# potinho.net
KiCad netlist of a schematic drawn in EAGLE
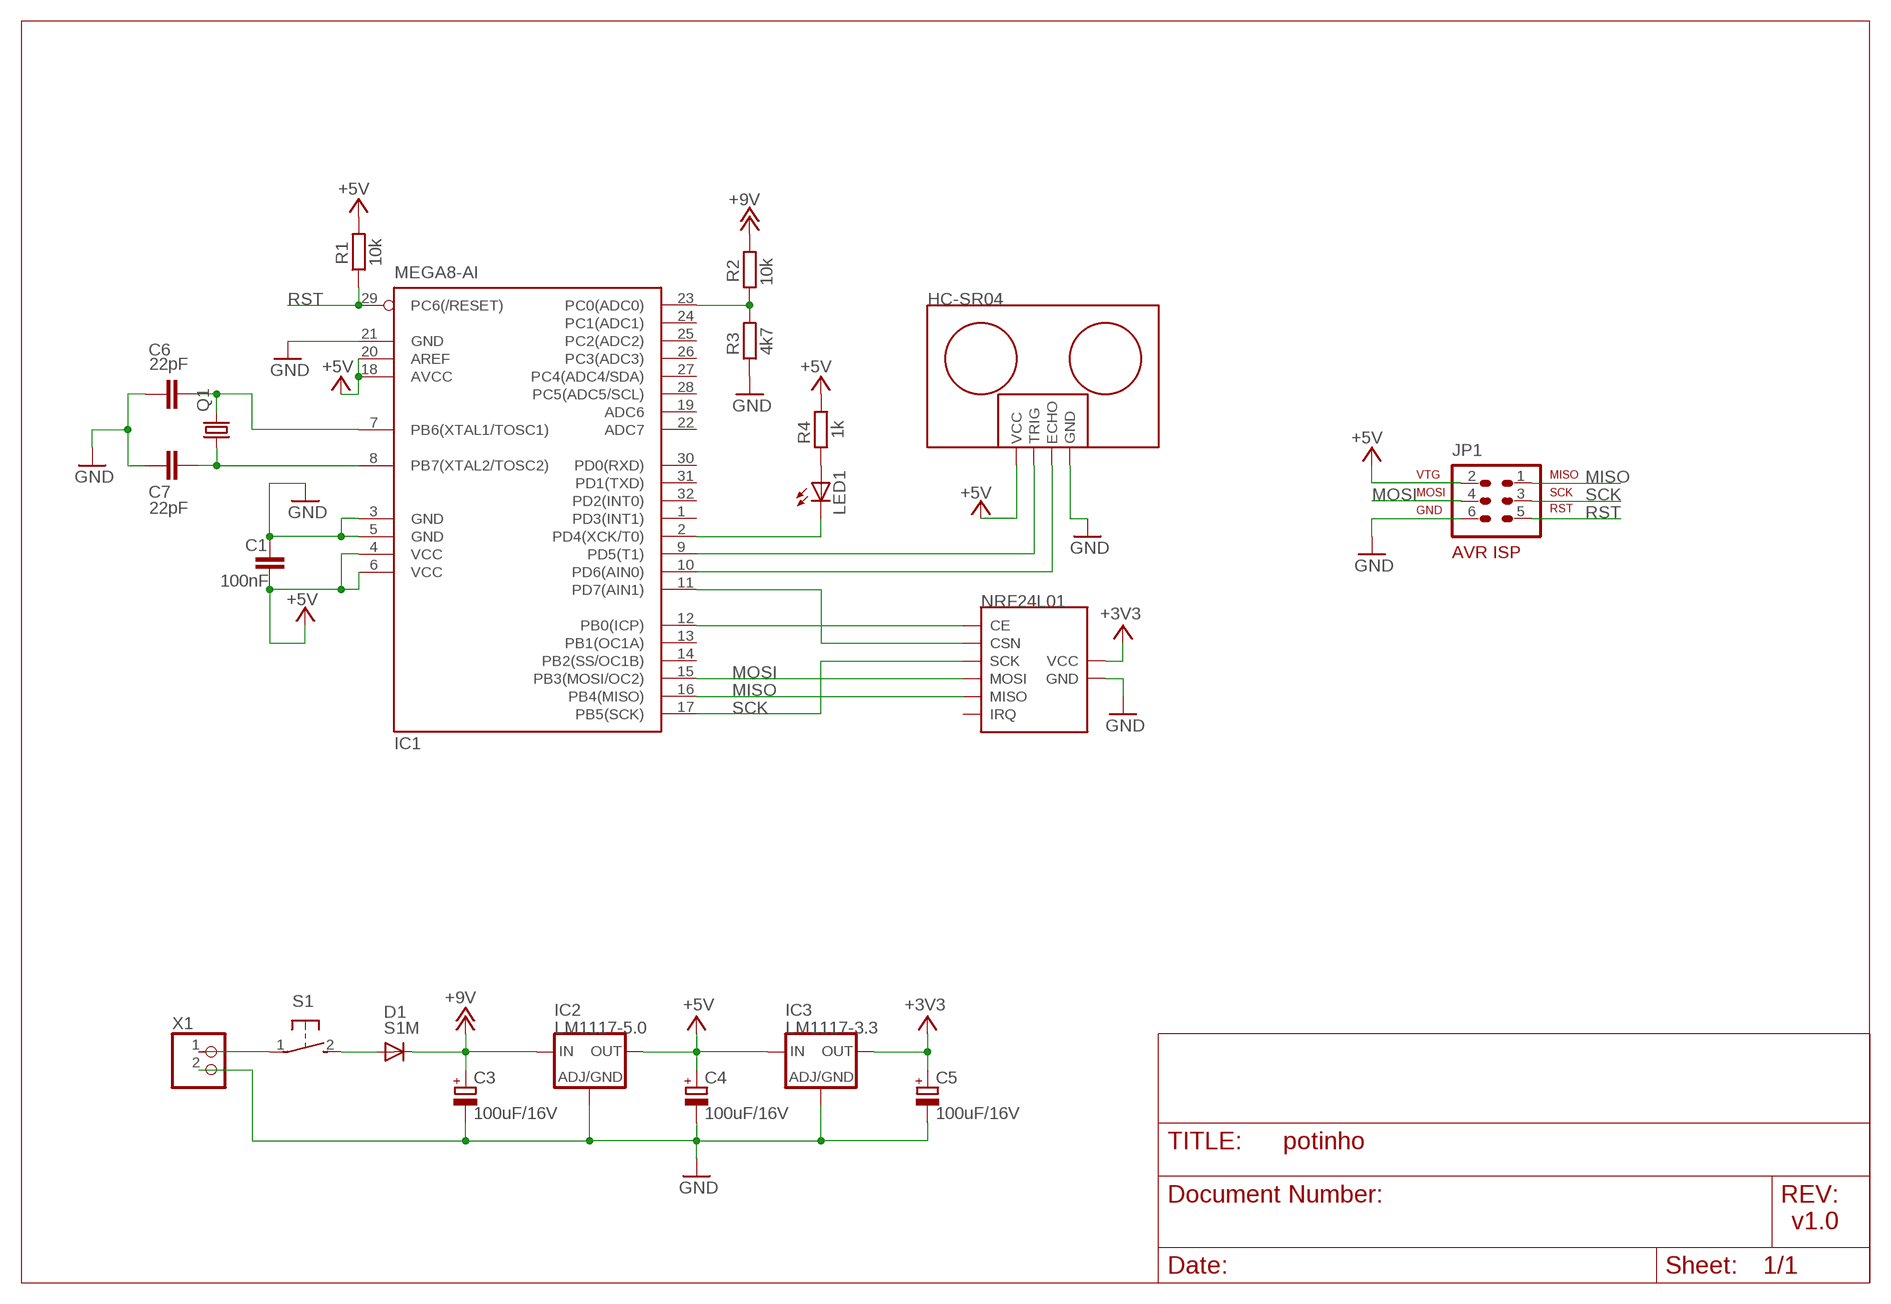
[diagram p0: schematic, sheet 1]

(export (version "E")
  (design (tool "Eeschema 10.0.6"))
  (components
    (comp (ref "C1")
      (value "100nF")
      (footprint "eagle-import:C0805K")
      (libsource (lib "eagle-import") (part "C-EUC0805K"))
    )
    (comp (ref "C3")
      (value "100uF/16V")
      (footprint "eagle-import:PANASONIC_D")
      (libsource (lib "eagle-import") (part "CPOL-EUPD"))
    )
    (comp (ref "C4")
      (value "100uF/16V")
      (footprint "eagle-import:PANASONIC_D")
      (libsource (lib "eagle-import") (part "CPOL-EUPD"))
    )
    (comp (ref "C5")
      (value "100uF/16V")
      (footprint "eagle-import:PANASONIC_D")
      (libsource (lib "eagle-import") (part "CPOL-EUPD"))
    )
    (comp (ref "C6")
      (value "22pF")
      (footprint "eagle-import:C0805K")
      (libsource (lib "eagle-import") (part "C-EUC0805K"))
    )
    (comp (ref "C7")
      (value "22pF")
      (footprint "eagle-import:C0805K")
      (libsource (lib "eagle-import") (part "C-EUC0805K"))
    )
    (comp (ref "D1")
      (value "S1M")
      (footprint "eagle-import:DO-214AC")
      (libsource (lib "eagle-import") (part "S1M"))
    )
    (comp (ref "IC1")
      (value "MEGA8-AI")
      (footprint "eagle-import:TQFP32-08")
      (fields (field (name "MPN") "ATMEGA8-16AU"))
      (libsource (lib "eagle-import") (part "MEGA8-AI"))
    )
    (comp (ref "IC2")
      (value "LM1117-5.0")
      (footprint "eagle-import:SOT223")
      (libsource (lib "eagle-import") (part "LM1117S"))
    )
    (comp (ref "IC3")
      (value "LM1117-3.3")
      (footprint "eagle-import:SOT223")
      (libsource (lib "eagle-import") (part "LM1117S"))
    )
    (comp (ref "IC4")
      (value "NRF24L01")
      (footprint "eagle-import:NRF24L01-MODULE")
      (libsource (lib "eagle-import") (part "NRF24L01-MODULE"))
    )
    (comp (ref "IC31")
      (value "HC-SR04")
      (footprint "eagle-import:1X04")
      (libsource (lib "eagle-import") (part "HC-SR04"))
    )
    (comp (ref "JP1")
      (value "AVR-ISP-6")
      (footprint "eagle-import:AVR-ISP-6")
      (libsource (lib "eagle-import") (part "AVR-ISP-6"))
    )
    (comp (ref "LED1")
      (value "LED3MM")
      (footprint "eagle-import:LED3MM")
      (libsource (lib "eagle-import") (part "LED3MM"))
    )
    (comp (ref "Q1")
      (value "CRYSTALHC49UP")
      (footprint "eagle-import:HC49UP")
      (libsource (lib "eagle-import") (part "CRYSTALHC49UP"))
    )
    (comp (ref "R1")
      (value "10k")
      (footprint "eagle-import:R0805")
      (libsource (lib "eagle-import") (part "R-EU_R0805"))
    )
    (comp (ref "R2")
      (value "10k")
      (footprint "eagle-import:0207_7")
      (libsource (lib "eagle-import") (part "R-EU_7"))
    )
    (comp (ref "R3")
      (value "4k7")
      (footprint "eagle-import:0207_7")
      (libsource (lib "eagle-import") (part "R-EU_7"))
    )
    (comp (ref "R4")
      (value "1k")
      (footprint "eagle-import:0207_7")
      (libsource (lib "eagle-import") (part "R-EU_7"))
    )
    (comp (ref "S1")
      (value "31-XX")
      (footprint "eagle-import:B3F-31XX")
      (fields (field (name "MPN") "B3F-3100"))
      (libsource (lib "eagle-import") (part "31-XX"))
    )
    (comp (ref "X1")
      (value "W237-102")
      (footprint "eagle-import:W237-102")
      (libsource (lib "eagle-import") (part "W237-102"))
    )
  )
  (nets
    (net (code "1") (name "+3V3") (class "Default")
      (node (ref "C5") (pin "+") (pinfunction "+_+") (pintype "passive"))
      (node (ref "IC3") (pin "2") (pinfunction "OUT_2") (pintype "passive"))
      (node (ref "IC3") (pin "4") (pinfunction "OUT_4") (pintype "passive"))
      (node (ref "IC4") (pin "2") (pinfunction "VCC_2") (pintype "power_in"))
    )
    (net (code "2") (name "+5V") (class "Default")
      (node (ref "C1") (pin "2") (pinfunction "2_2") (pintype "passive"))
      (node (ref "C4") (pin "+") (pinfunction "+_+") (pintype "passive"))
      (node (ref "IC1") (pin "18") (pinfunction "AVCC_18") (pintype "power_in"))
      (node (ref "IC1") (pin "20") (pinfunction "AREF_20") (pintype "passive"))
      (node (ref "IC1") (pin "4") (pinfunction "VCC_4") (pintype "power_in"))
      (node (ref "IC1") (pin "6") (pinfunction "VCC_6") (pintype "power_in"))
      (node (ref "IC2") (pin "2") (pinfunction "OUT_2") (pintype "passive"))
      (node (ref "IC2") (pin "4") (pinfunction "OUT_4") (pintype "passive"))
      (node (ref "IC3") (pin "3") (pinfunction "IN_3") (pintype "input"))
      (node (ref "IC31") (pin "1") (pinfunction "VCC_1") (pintype "power_in"))
      (node (ref "JP1") (pin "2") (pinfunction "VTG_2") (pintype "passive"))
      (node (ref "R1") (pin "2") (pinfunction "2_2") (pintype "passive"))
      (node (ref "R4") (pin "2") (pinfunction "2_2") (pintype "passive"))
    )
    (net (code "3") (name "+9V") (class "Default")
      (node (ref "C3") (pin "+") (pinfunction "+_+") (pintype "passive"))
      (node (ref "D1") (pin "C") (pinfunction "C_C") (pintype "passive"))
      (node (ref "IC2") (pin "3") (pinfunction "IN_3") (pintype "input"))
      (node (ref "R2") (pin "2") (pinfunction "2_2") (pintype "passive"))
    )
    (net (code "4") (name "/MISO") (class "Default")
      (node (ref "IC1") (pin "16") (pinfunction "PB4(MISO)_16") (pintype "bidirectional"))
      (node (ref "IC4") (pin "7") (pinfunction "MISO_7") (pintype "bidirectional"))
      (node (ref "JP1") (pin "1") (pinfunction "MISO_1") (pintype "passive"))
    )
    (net (code "5") (name "/MOSI") (class "Default")
      (node (ref "IC1") (pin "15") (pinfunction "PB3(MOSI/OC2)_15") (pintype "bidirectional"))
      (node (ref "IC4") (pin "6") (pinfunction "MOSI_6") (pintype "bidirectional"))
      (node (ref "JP1") (pin "4") (pinfunction "MOSI_4") (pintype "passive"))
    )
    (net (code "6") (name "/RST") (class "Default")
      (node (ref "IC1") (pin "29") (pinfunction "PC6(/RESET)_29") (pintype "bidirectional"))
      (node (ref "JP1") (pin "5") (pinfunction "RST_5") (pintype "passive"))
      (node (ref "R1") (pin "1") (pinfunction "1_1") (pintype "passive"))
    )
    (net (code "7") (name "/SCK") (class "Default")
      (node (ref "IC1") (pin "17") (pinfunction "PB5(SCK)_17") (pintype "bidirectional"))
      (node (ref "IC4") (pin "5") (pinfunction "SCK_5") (pintype "bidirectional"))
      (node (ref "JP1") (pin "3") (pinfunction "SCK_3") (pintype "passive"))
    )
    (net (code "8") (name "GND") (class "Default")
      (node (ref "C1") (pin "1") (pinfunction "1_1") (pintype "passive"))
      (node (ref "C3") (pin "-") (pinfunction "-_-") (pintype "passive"))
      (node (ref "C4") (pin "-") (pinfunction "-_-") (pintype "passive"))
      (node (ref "C5") (pin "-") (pinfunction "-_-") (pintype "passive"))
      (node (ref "C6") (pin "1") (pinfunction "1_1") (pintype "passive"))
      (node (ref "C7") (pin "1") (pinfunction "1_1") (pintype "passive"))
      (node (ref "IC1") (pin "21") (pinfunction "GND_21") (pintype "power_in"))
      (node (ref "IC1") (pin "3") (pinfunction "GND_3") (pintype "power_in"))
      (node (ref "IC1") (pin "5") (pinfunction "GND_5") (pintype "power_in"))
      (node (ref "IC2") (pin "1") (pinfunction "ADJ_1") (pintype "input"))
      (node (ref "IC3") (pin "1") (pinfunction "ADJ_1") (pintype "input"))
      (node (ref "IC31") (pin "4") (pinfunction "GND_4") (pintype "power_in"))
      (node (ref "IC4") (pin "1") (pinfunction "GND_1") (pintype "power_in"))
      (node (ref "JP1") (pin "6") (pinfunction "GND_6") (pintype "passive"))
      (node (ref "R3") (pin "1") (pinfunction "1_1") (pintype "passive"))
      (node (ref "X1") (pin "2") (pinfunction "2_2") (pintype "passive"))
    )
    (net (code "9") (name "Net-(IC1-PB0(ICP))") (class "Default")
      (node (ref "IC1") (pin "12") (pinfunction "PB0(ICP)_12") (pintype "bidirectional"))
      (node (ref "IC4") (pin "3") (pinfunction "CE_3") (pintype "bidirectional"))
    )
    (net (code "10") (name "Net-(IC1-PB6(XTAL1{slash}TOSC1))") (class "Default")
      (node (ref "C6") (pin "2") (pinfunction "2_2") (pintype "passive"))
      (node (ref "IC1") (pin "7") (pinfunction "PB6(XTAL1/TOSC1)_7") (pintype "bidirectional"))
      (node (ref "Q1") (pin "2") (pinfunction "2_2") (pintype "passive"))
    )
    (net (code "11") (name "Net-(IC1-PB7(XTAL2{slash}TOSC2))") (class "Default")
      (node (ref "C7") (pin "2") (pinfunction "2_2") (pintype "passive"))
      (node (ref "IC1") (pin "8") (pinfunction "PB7(XTAL2/TOSC2)_8") (pintype "bidirectional"))
      (node (ref "Q1") (pin "1") (pinfunction "1_1") (pintype "passive"))
    )
    (net (code "12") (name "Net-(IC1-PC0(ADC0))") (class "Default")
      (node (ref "IC1") (pin "23") (pinfunction "PC0(ADC0)_23") (pintype "bidirectional"))
      (node (ref "R2") (pin "1") (pinfunction "1_1") (pintype "passive"))
      (node (ref "R3") (pin "2") (pinfunction "2_2") (pintype "passive"))
    )
    (net (code "13") (name "Net-(IC1-PD4(XCK{slash}T0))") (class "Default")
      (node (ref "IC1") (pin "2") (pinfunction "PD4(XCK/T0)_2") (pintype "bidirectional"))
      (node (ref "LED1") (pin "K") (pinfunction "C_K") (pintype "passive"))
    )
    (net (code "14") (name "Net-(IC1-PD5(T1))") (class "Default")
      (node (ref "IC1") (pin "9") (pinfunction "PD5(T1)_9") (pintype "bidirectional"))
      (node (ref "IC31") (pin "2") (pinfunction "TRIG_2") (pintype "bidirectional"))
    )
    (net (code "15") (name "Net-(IC1-PD6(AIN0))") (class "Default")
      (node (ref "IC1") (pin "10") (pinfunction "PD6(AIN0)_10") (pintype "bidirectional"))
      (node (ref "IC31") (pin "3") (pinfunction "ECHO_3") (pintype "bidirectional"))
    )
    (net (code "16") (name "Net-(IC1-PD7(AIN1))") (class "Default")
      (node (ref "IC1") (pin "11") (pinfunction "PD7(AIN1)_11") (pintype "bidirectional"))
      (node (ref "IC4") (pin "4") (pinfunction "CSN_4") (pintype "bidirectional"))
    )
    (net (code "17") (name "Net-(LED1-PadA)") (class "Default")
      (node (ref "LED1") (pin "A") (pinfunction "A_A") (pintype "passive"))
      (node (ref "R4") (pin "1") (pinfunction "1_1") (pintype "passive"))
    )
    (net (code "18") (name "Net-(S1-P)") (class "Default")
      (node (ref "S1") (pin "1") (pinfunction "P_1") (pintype "passive"))
      (node (ref "X1") (pin "1") (pinfunction "1_1") (pintype "passive"))
    )
    (net (code "19") (name "Net-(S1-S)") (class "Default")
      (node (ref "D1") (pin "A") (pinfunction "A_A") (pintype "passive"))
      (node (ref "S1") (pin "2") (pinfunction "S_2") (pintype "passive"))
    )
    (net (code "20") (name "unconnected-(IC1-ADC6-Pad19)") (class "Default")
      (node (ref "IC1") (pin "19") (pinfunction "ADC6_19") (pintype "bidirectional"))
    )
    (net (code "21") (name "unconnected-(IC1-ADC7-Pad22)") (class "Default")
      (node (ref "IC1") (pin "22") (pinfunction "ADC7_22") (pintype "bidirectional"))
    )
    (net (code "22") (name "unconnected-(IC1-PB1(OC1A)-Pad13)") (class "Default")
      (node (ref "IC1") (pin "13") (pinfunction "PB1(OC1A)_13") (pintype "bidirectional"))
    )
    (net (code "23") (name "unconnected-(IC1-PB2(SS{slash}OC1B)-Pad14)") (class "Default")
      (node (ref "IC1") (pin "14") (pinfunction "PB2(SS/OC1B)_14") (pintype "bidirectional"))
    )
    (net (code "24") (name "unconnected-(IC1-PC1(ADC1)-Pad24)") (class "Default")
      (node (ref "IC1") (pin "24") (pinfunction "PC1(ADC1)_24") (pintype "bidirectional"))
    )
    (net (code "25") (name "unconnected-(IC1-PC2(ADC2)-Pad25)") (class "Default")
      (node (ref "IC1") (pin "25") (pinfunction "PC2(ADC2)_25") (pintype "bidirectional"))
    )
    (net (code "26") (name "unconnected-(IC1-PC3(ADC3)-Pad26)") (class "Default")
      (node (ref "IC1") (pin "26") (pinfunction "PC3(ADC3)_26") (pintype "bidirectional"))
    )
    (net (code "27") (name "unconnected-(IC1-PC4(ADC4{slash}SDA)-Pad27)") (class "Default")
      (node (ref "IC1") (pin "27") (pinfunction "PC4(ADC4/SDA)_27") (pintype "bidirectional"))
    )
    (net (code "28") (name "unconnected-(IC1-PC5(ADC5{slash}SCL)-Pad28)") (class "Default")
      (node (ref "IC1") (pin "28") (pinfunction "PC5(ADC5/SCL)_28") (pintype "bidirectional"))
    )
    (net (code "29") (name "unconnected-(IC1-PD0(RXD)-Pad30)") (class "Default")
      (node (ref "IC1") (pin "30") (pinfunction "PD0(RXD)_30") (pintype "bidirectional"))
    )
    (net (code "30") (name "unconnected-(IC1-PD1(TXD)-Pad31)") (class "Default")
      (node (ref "IC1") (pin "31") (pinfunction "PD1(TXD)_31") (pintype "bidirectional"))
    )
    (net (code "31") (name "unconnected-(IC1-PD2(INT0)-Pad32)") (class "Default")
      (node (ref "IC1") (pin "32") (pinfunction "PD2(INT0)_32") (pintype "bidirectional"))
    )
    (net (code "32") (name "unconnected-(IC1-PD3(INT1)-Pad1)") (class "Default")
      (node (ref "IC1") (pin "1") (pinfunction "PD3(INT1)_1") (pintype "bidirectional"))
    )
    (net (code "33") (name "unconnected-(IC4-IRQ-Pad8)") (class "Default")
      (node (ref "IC4") (pin "8") (pinfunction "IRQ_8") (pintype "bidirectional"))
    )
  )
)
